# SMARC_CON.net
KiCad netlist of a schematic drawn in Altium Designer
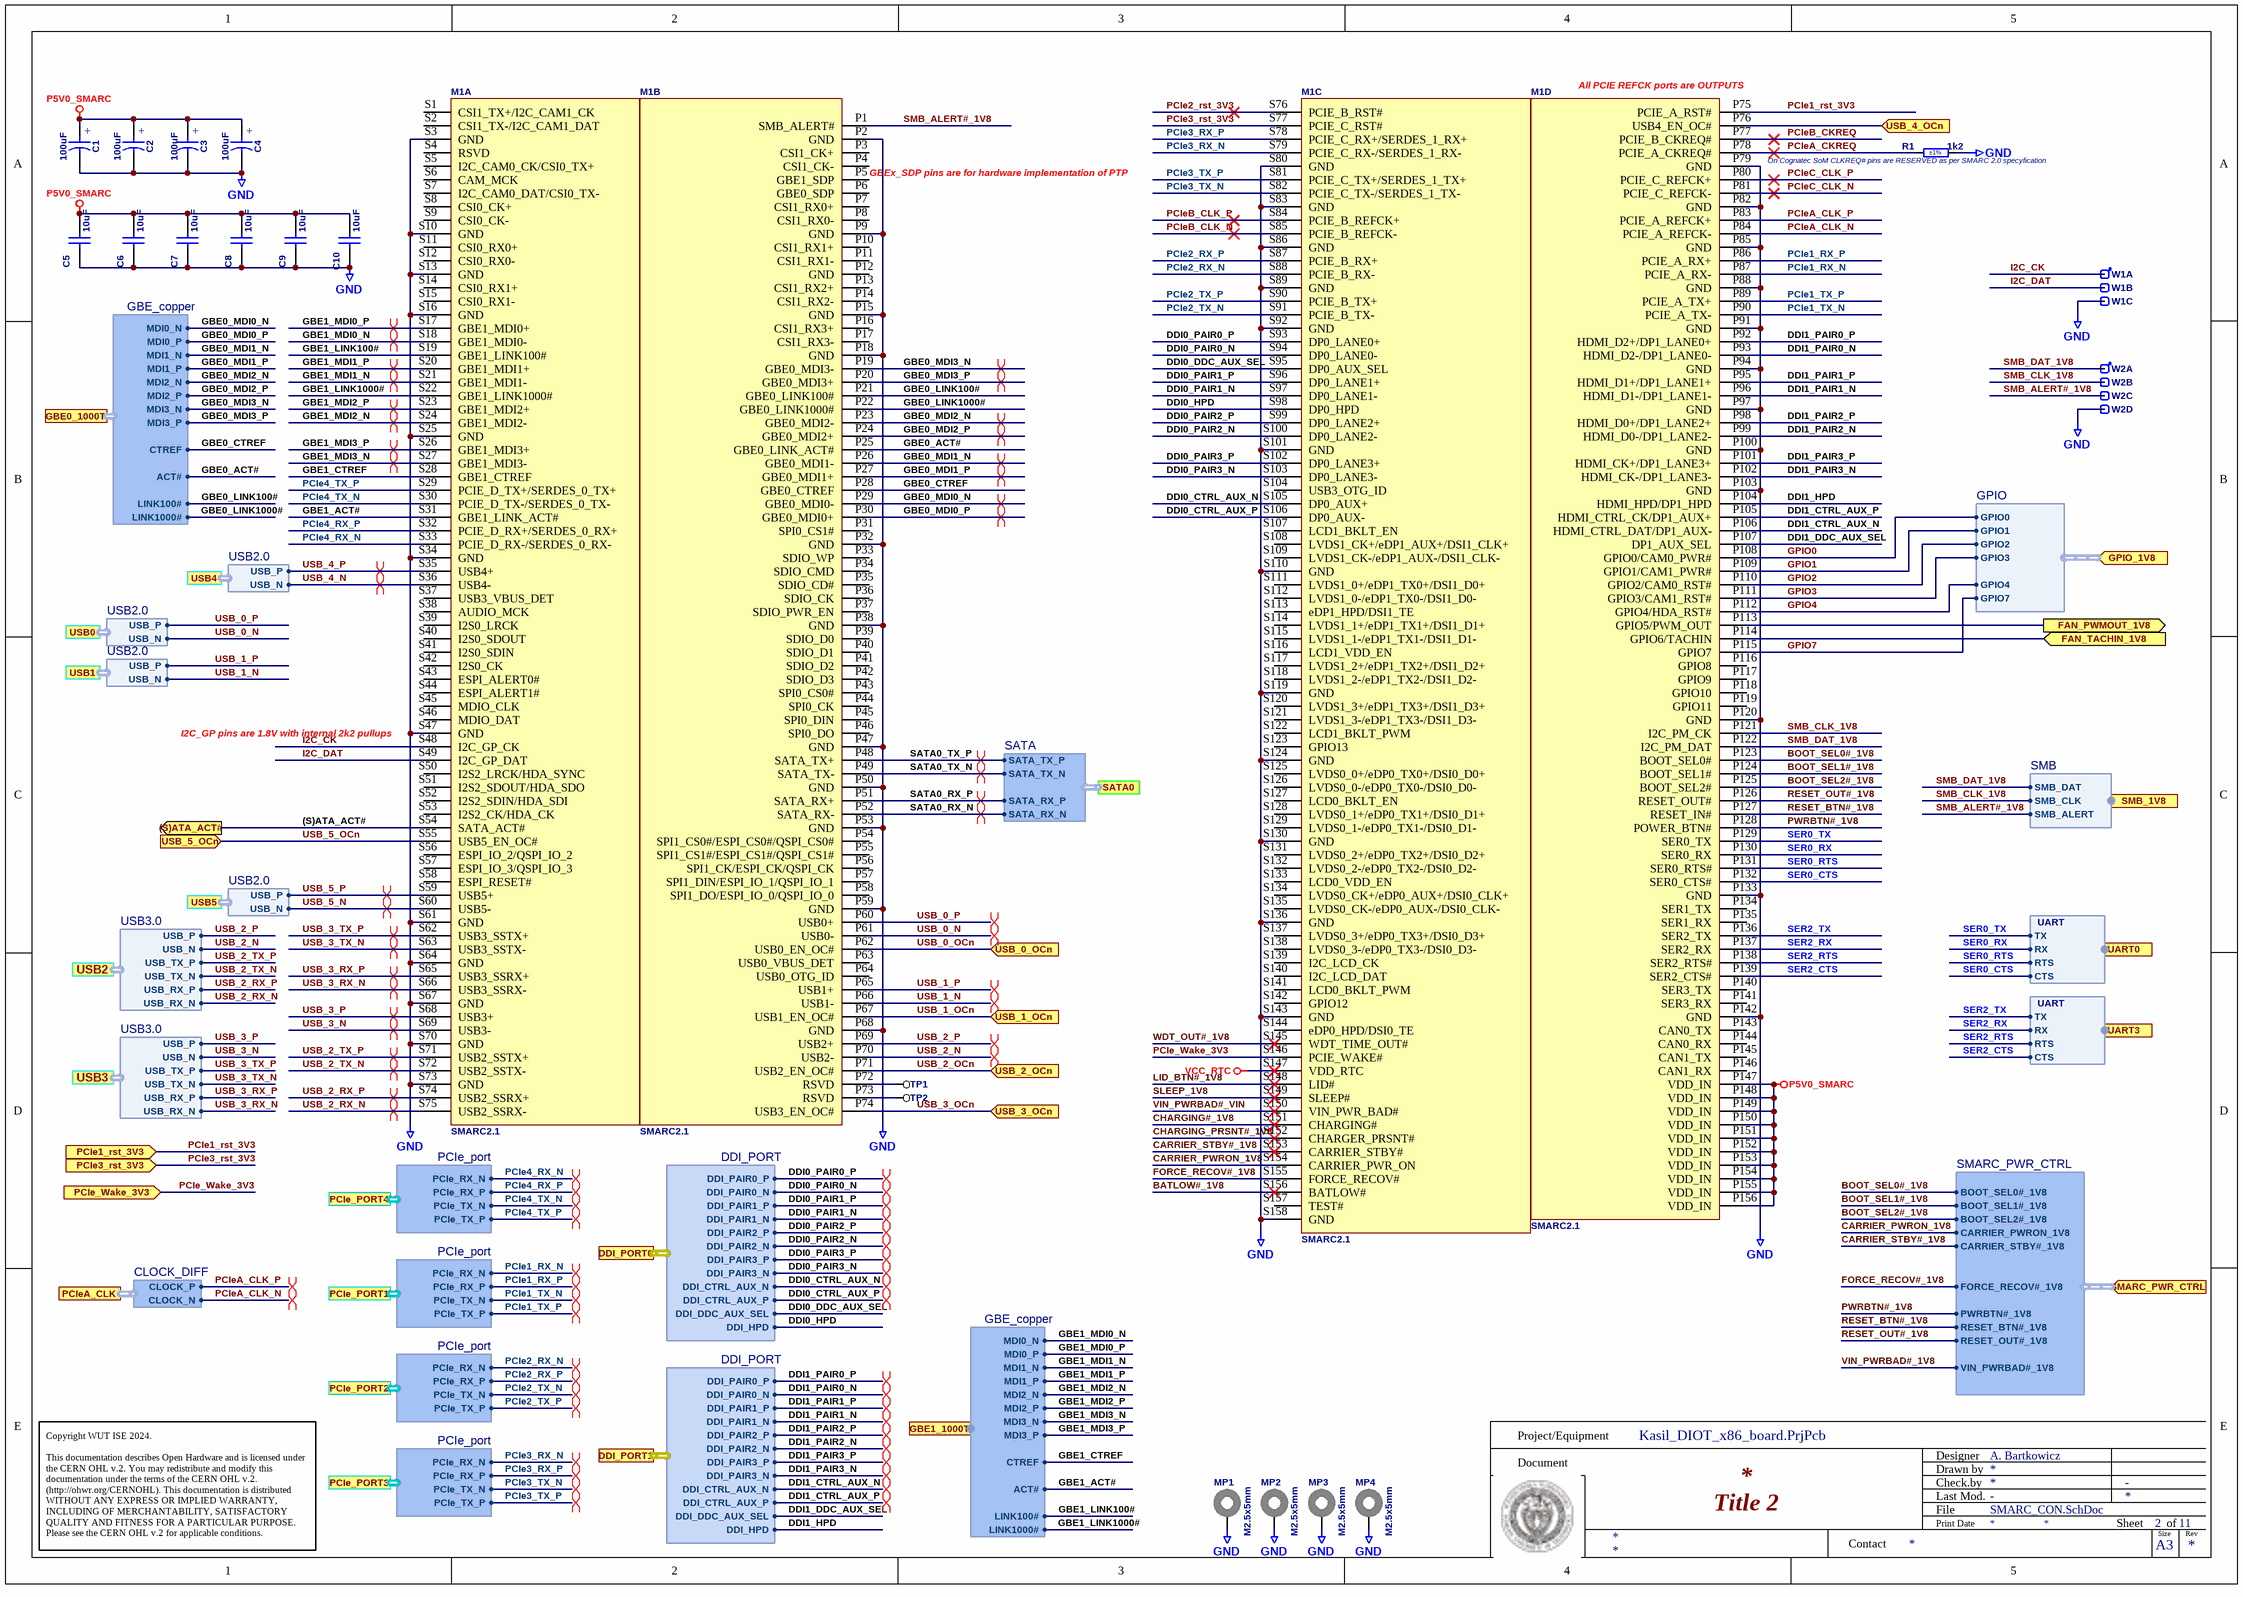
[diagram p0: SMARC_CON.SchDoc]

(export (version "E")
  (design (tool "Eeschema 10.0.6"))
  (components
    (comp (ref "C1")
      (value "100uF")
      (footprint "CAPMP7343X310N")
      (description "Polarised capacitor")
      (fields
        (field (name "PART NUMBER") "CTE7343-31_100UF_16V_10%_LESR0100")
        (field (name "VOLTAGE") "16V")
        (field (name "AUTHOR") "CERN DEM JLC")
      )
      (libsource (lib "Capacitors") (part "Capacitor - polarized"))
    )
    (comp (ref "C2")
      (value "100uF")
      (footprint "CAPMP7343X310N")
      (description "Polarised capacitor")
      (fields
        (field (name "PART NUMBER") "CTE7343-31_100UF_16V_10%_LESR0100")
        (field (name "VOLTAGE") "16V")
        (field (name "AUTHOR") "CERN DEM JLC")
      )
      (libsource (lib "Capacitors") (part "Capacitor - polarized"))
    )
    (comp (ref "C3")
      (value "100uF")
      (footprint "CAPMP7343X310N")
      (description "Polarised capacitor")
      (fields
        (field (name "PART NUMBER") "CTE7343-31_100UF_16V_10%_LESR0100")
        (field (name "VOLTAGE") "16V")
        (field (name "AUTHOR") "CERN DEM JLC")
      )
      (libsource (lib "Capacitors") (part "Capacitor - polarized"))
    )
    (comp (ref "C4")
      (value "100uF")
      (footprint "CAPMP7343X310N")
      (description "Polarised capacitor")
      (fields
        (field (name "PART NUMBER") "CTE7343-31_100UF_16V_10%_LESR0100")
        (field (name "VOLTAGE") "16V")
        (field (name "AUTHOR") "CERN DEM JLC")
      )
      (libsource (lib "Capacitors") (part "Capacitor - polarized"))
    )
    (comp (ref "C5")
      (value "10uF")
      (footprint "CAPC1608X80N")
      (description "Non-polarised capacitor")
      (fields
        (field (name "PART NUMBER") "CC0603_10UF_16V_20%_X5R")
        (field (name "VOLTAGE") "16V")
        (field (name "AUTHOR") "CERN DEM MR")
      )
      (libsource (lib "Capacitors") (part "Capacitor - non polarized"))
    )
    (comp (ref "C6")
      (value "10uF")
      (footprint "CAPC1608X80N")
      (description "Non-polarised capacitor")
      (fields
        (field (name "PART NUMBER") "CC0603_10UF_16V_20%_X5R")
        (field (name "VOLTAGE") "16V")
        (field (name "AUTHOR") "CERN DEM MR")
      )
      (libsource (lib "Capacitors") (part "Capacitor - non polarized"))
    )
    (comp (ref "C7")
      (value "10uF")
      (footprint "CAPC1608X80N")
      (description "Non-polarised capacitor")
      (fields
        (field (name "PART NUMBER") "CC0603_10UF_16V_20%_X5R")
        (field (name "VOLTAGE") "16V")
        (field (name "AUTHOR") "CERN DEM MR")
      )
      (libsource (lib "Capacitors") (part "Capacitor - non polarized"))
    )
    (comp (ref "C8")
      (value "10uF")
      (footprint "CAPC1608X80N")
      (description "Non-polarised capacitor")
      (fields
        (field (name "PART NUMBER") "CC0603_10UF_16V_20%_X5R")
        (field (name "VOLTAGE") "16V")
        (field (name "AUTHOR") "CERN DEM MR")
      )
      (libsource (lib "Capacitors") (part "Capacitor - non polarized"))
    )
    (comp (ref "C9")
      (value "10uF")
      (footprint "CAPC1608X80N")
      (description "Non-polarised capacitor")
      (fields
        (field (name "PART NUMBER") "CC0603_10UF_16V_20%_X5R")
        (field (name "VOLTAGE") "16V")
        (field (name "AUTHOR") "CERN DEM MR")
      )
      (libsource (lib "Capacitors") (part "Capacitor - non polarized"))
    )
    (comp (ref "C10")
      (value "10uF")
      (footprint "CAPC1608X80N")
      (description "Non-polarised capacitor")
      (fields
        (field (name "PART NUMBER") "CC0603_10UF_16V_20%_X5R")
        (field (name "VOLTAGE") "16V")
        (field (name "AUTHOR") "CERN DEM MR")
      )
      (libsource (lib "Capacitors") (part "Capacitor - non polarized"))
    )
    (comp (ref "M1") (value "SMARC2.1") (footprint "SMARC2.1") (libsource (lib "") (part "SMARC2.1_1")))
    (comp (ref "MP1")
      (value "M2.5x5mm")
      (footprint "9774025151")
      (description "WA-SMSI SMT Steel Spacer, internal Thread, OD 5.1mm, M2.5x5mm")
      (fields (field (name "MANUFACTURER 1 PART NUMBER") "9774050151R"))
      (libsource (lib "Altium_WA-SMSI (rev21a)") (part "9774050151R"))
    )
    (comp (ref "MP2")
      (value "M2.5x5mm")
      (footprint "9774025151")
      (description "WA-SMSI SMT Steel Spacer, internal Thread, OD 5.1mm, M2.5x5mm")
      (fields (field (name "MANUFACTURER 1 PART NUMBER") "9774050151R"))
      (libsource (lib "Altium_WA-SMSI (rev21a)") (part "9774050151R"))
    )
    (comp (ref "MP3")
      (value "M2.5x5mm")
      (footprint "9774025151")
      (description "WA-SMSI SMT Steel Spacer, internal Thread, OD 5.1mm, M2.5x5mm")
      (fields (field (name "MANUFACTURER 1 PART NUMBER") "9774050151R"))
      (libsource (lib "Altium_WA-SMSI (rev21a)") (part "9774050151R"))
    )
    (comp (ref "MP4")
      (value "M2.5x5mm")
      (footprint "9774025151")
      (description "WA-SMSI SMT Steel Spacer, internal Thread, OD 5.1mm, M2.5x5mm")
      (fields (field (name "MANUFACTURER 1 PART NUMBER") "9774050151R"))
      (libsource (lib "Altium_WA-SMSI (rev21a)") (part "9774050151R"))
    )
    (comp (ref "R1")
      (value "1k2")
      (footprint "RESC1005X40N")
      (description "Resistor - 1%")
      (fields
        (field (name "TOLERANCE") "±1%")
        (field (name "PART NUMBER") "R0402_1K2_1%_0.0625W_100PPM")
        (field (name "POWER") "0.0625W")
        (field (name "AUTHOR") "CERN DEM JLC")
      )
      (libsource (lib "Resistors") (part "Resistor - 1%"))
    )
    (comp (ref "TP1")
      (value "TP")
      (footprint "TP_large")
      (description "Testpoint")
      (libsource (lib "LIBRARY_SCH") (part "TP"))
    )
    (comp (ref "TP2")
      (value "TP")
      (footprint "TP_large")
      (description "Testpoint")
      (libsource (lib "LIBRARY_SCH") (part "TP"))
    )
    (comp (ref "W1")
      (value "Header 3")
      (footprint "SAMTEC_TSW-103-23-L-S")
      (description "3 Mini Wire-Wrap Contact Strip Header")
      (fields
        (field (name "PART NUMBER") "SAMTEC_TSW-103-23-L-S")
        (field (name "MANUFACTURER") "SAMTEC")
        (field (name "AUTHOR") "CERN DEM JLC")
      )
      (libsource (lib "Connectors") (part "Wire-Wrap Contact x3"))
    )
    (comp (ref "W2")
      (value "Header 4")
      (footprint "SAMTEC_TSW-104-23-L-S")
      (description "4 Mini Wire-Wrap Contact Strip Header")
      (fields
        (field (name "PART NUMBER") "SAMTEC_TSW-104-23-L-S")
        (field (name "MANUFACTURER") "SAMTEC")
        (field (name "AUTHOR") "CERN DEM JLC")
      )
      (libsource (lib "Connectors") (part "Wire-Wrap Contact x4"))
    )
  )
  (nets
    (net (code "12") (name "/(S)ATA_ACT#") (class "Default")
      (node (ref "M1") (pin "S54") (pinfunction "SATA_ACT#_S54") (pintype "passive"))
    )
    (net (code "13") (name "/BATLOW#_1V8") (class "Default")
      (node (ref "M1") (pin "S156") (pinfunction "BATLOW#_S156") (pintype "passive+no_connect"))
    )
    (net (code "14") (name "/BOOT_SEL0#_1V8") (class "Default")
      (node (ref "M1") (pin "P123") (pinfunction "BOOT_SEL0#_P123") (pintype "passive"))
    )
    (net (code "15") (name "/BOOT_SEL1#_1V8") (class "Default")
      (node (ref "M1") (pin "P124") (pinfunction "BOOT_SEL1#_P124") (pintype "passive"))
    )
    (net (code "16") (name "/BOOT_SEL2#_1V8") (class "Default")
      (node (ref "M1") (pin "P125") (pinfunction "BOOT_SEL2#_P125") (pintype "passive"))
    )
    (net (code "17") (name "/CARRIER_PWRON_1V8") (class "Default")
      (node (ref "M1") (pin "S154") (pinfunction "CARRIER_PWR_ON_S154") (pintype "passive"))
    )
    (net (code "18") (name "/CARRIER_STBY#_1V8") (class "Default")
      (node (ref "M1") (pin "S153") (pinfunction "CARRIER_STBY#_S153") (pintype "passive+no_connect"))
    )
    (net (code "19") (name "/CHARGING#_1V8") (class "Default")
      (node (ref "M1") (pin "S151") (pinfunction "CHARGING#_S151") (pintype "passive+no_connect"))
    )
    (net (code "20") (name "/CHARGING_PRSNT#_1V8") (class "Default")
      (node (ref "M1") (pin "S152") (pinfunction "CHARGER_PRSNT#_S152") (pintype "passive+no_connect"))
    )
    (net (code "21") (name "/DDI0_CTRL_AUX_N") (class "Default")
      (node (ref "M1") (pin "S105") (pinfunction "DP0_AUX+_S105") (pintype "passive"))
    )
    (net (code "22") (name "/DDI0_CTRL_AUX_P") (class "Default")
      (node (ref "M1") (pin "S106") (pinfunction "DP0_AUX-_S106") (pintype "passive"))
    )
    (net (code "23") (name "/DDI0_DDC_AUX_SEL") (class "Default")
      (node (ref "M1") (pin "S95") (pinfunction "DP0_AUX_SEL_S95") (pintype "passive"))
    )
    (net (code "24") (name "/DDI0_HPD") (class "Default")
      (node (ref "M1") (pin "S98") (pinfunction "DP0_HPD_S98") (pintype "passive"))
    )
    (net (code "25") (name "/DDI0_PAIR0_N") (class "Default")
      (node (ref "M1") (pin "S94") (pinfunction "DP0_LANE0-_S94") (pintype "passive"))
    )
    (net (code "26") (name "/DDI0_PAIR0_P") (class "Default")
      (node (ref "M1") (pin "S93") (pinfunction "DP0_LANE0+_S93") (pintype "passive"))
    )
    (net (code "27") (name "/DDI0_PAIR1_N") (class "Default")
      (node (ref "M1") (pin "S97") (pinfunction "DP0_LANE1-_S97") (pintype "passive"))
    )
    (net (code "28") (name "/DDI0_PAIR1_P") (class "Default")
      (node (ref "M1") (pin "S96") (pinfunction "DP0_LANE1+_S96") (pintype "passive"))
    )
    (net (code "29") (name "/DDI0_PAIR2_N") (class "Default")
      (node (ref "M1") (pin "S100") (pinfunction "DP0_LANE2-_S100") (pintype "passive"))
    )
    (net (code "30") (name "/DDI0_PAIR2_P") (class "Default")
      (node (ref "M1") (pin "S99") (pinfunction "DP0_LANE2+_S99") (pintype "passive"))
    )
    (net (code "31") (name "/DDI0_PAIR3_N") (class "Default")
      (node (ref "M1") (pin "S103") (pinfunction "DP0_LANE3-_S103") (pintype "passive"))
    )
    (net (code "32") (name "/DDI0_PAIR3_P") (class "Default")
      (node (ref "M1") (pin "S102") (pinfunction "DP0_LANE3+_S102") (pintype "passive"))
    )
    (net (code "33") (name "/DDI1_CTRL_AUX_N") (class "Default")
      (node (ref "M1") (pin "P106") (pinfunction "HDMI_CTRL_DAT/DP1_AUX-_P106") (pintype "passive"))
    )
    (net (code "34") (name "/DDI1_CTRL_AUX_P") (class "Default")
      (node (ref "M1") (pin "P105") (pinfunction "HDMI_CTRL_CK/DP1_AUX+_P105") (pintype "passive"))
    )
    (net (code "35") (name "/DDI1_DDC_AUX_SEL") (class "Default")
      (node (ref "M1") (pin "P107") (pinfunction "DP1_AUX_SEL_P107") (pintype "passive"))
    )
    (net (code "36") (name "/DDI1_HPD") (class "Default")
      (node (ref "M1") (pin "P104") (pinfunction "HDMI_HPD/DP1_HPD_P104") (pintype "passive"))
    )
    (net (code "37") (name "/DDI1_PAIR0_N") (class "Default")
      (node (ref "M1") (pin "P93") (pinfunction "HDMI_D2-/DP1_LANE0-_P93") (pintype "passive"))
    )
    (net (code "38") (name "/DDI1_PAIR0_P") (class "Default")
      (node (ref "M1") (pin "P92") (pinfunction "HDMI_D2+/DP1_LANE0+_P92") (pintype "passive"))
    )
    (net (code "39") (name "/DDI1_PAIR1_N") (class "Default")
      (node (ref "M1") (pin "P96") (pinfunction "HDMI_D1-/DP1_LANE1-_P96") (pintype "passive"))
    )
    (net (code "40") (name "/DDI1_PAIR1_P") (class "Default")
      (node (ref "M1") (pin "P95") (pinfunction "HDMI_D1+/DP1_LANE1+_P95") (pintype "passive"))
    )
    (net (code "41") (name "/DDI1_PAIR2_N") (class "Default")
      (node (ref "M1") (pin "P99") (pinfunction "HDMI_D0-/DP1_LANE2-_P99") (pintype "passive"))
    )
    (net (code "42") (name "/DDI1_PAIR2_P") (class "Default")
      (node (ref "M1") (pin "P98") (pinfunction "HDMI_D0+/DP1_LANE2+_P98") (pintype "passive"))
    )
    (net (code "43") (name "/DDI1_PAIR3_N") (class "Default")
      (node (ref "M1") (pin "P102") (pinfunction "HDMI_CK-/DP1_LANE3-_P102") (pintype "passive"))
    )
    (net (code "44") (name "/DDI1_PAIR3_P") (class "Default")
      (node (ref "M1") (pin "P101") (pinfunction "HDMI_CK+/DP1_LANE3+_P101") (pintype "passive"))
    )
    (net (code "45") (name "/FAN_PWMOUT_1V8") (class "Default")
      (node (ref "M1") (pin "P113") (pinfunction "GPIO5/PWM_OUT_P113") (pintype "passive"))
    )
    (net (code "46") (name "/FAN_TACHIN_1V8") (class "Default")
      (node (ref "M1") (pin "P114") (pinfunction "GPIO6/TACHIN_P114") (pintype "passive"))
    )
    (net (code "47") (name "/FORCE_RECOV#_1V8") (class "Default")
      (node (ref "M1") (pin "S155") (pinfunction "FORCE_RECOV#_S155") (pintype "passive"))
    )
    (net (code "48") (name "/GBE0_ACT#") (class "Default")
      (node (ref "M1") (pin "P25") (pinfunction "GBE0_LINK_ACT#_P25") (pintype "passive"))
    )
    (net (code "49") (name "/GBE0_CTREF") (class "Default")
      (node (ref "M1") (pin "P28") (pinfunction "GBE0_CTREF_P28") (pintype "passive"))
    )
    (net (code "50") (name "/GBE0_LINK100#") (class "Default")
      (node (ref "M1") (pin "P21") (pinfunction "GBE0_LINK100#_P21") (pintype "passive"))
    )
    (net (code "51") (name "/GBE0_LINK1000#") (class "Default")
      (node (ref "M1") (pin "P22") (pinfunction "GBE0_LINK1000#_P22") (pintype "passive"))
    )
    (net (code "52") (name "/GBE0_MDI0_N") (class "Default")
      (node (ref "M1") (pin "P29") (pinfunction "GBE0_MDI0-_P29") (pintype "passive"))
    )
    (net (code "53") (name "/GBE0_MDI0_P") (class "Default")
      (node (ref "M1") (pin "P30") (pinfunction "GBE0_MDI0+_P30") (pintype "passive"))
    )
    (net (code "54") (name "/GBE0_MDI1_N") (class "Default")
      (node (ref "M1") (pin "P26") (pinfunction "GBE0_MDI1-_P26") (pintype "passive"))
    )
    (net (code "55") (name "/GBE0_MDI1_P") (class "Default")
      (node (ref "M1") (pin "P27") (pinfunction "GBE0_MDI1+_P27") (pintype "passive"))
    )
    (net (code "56") (name "/GBE0_MDI2_N") (class "Default")
      (node (ref "M1") (pin "P23") (pinfunction "GBE0_MDI2-_P23") (pintype "passive"))
    )
    (net (code "57") (name "/GBE0_MDI2_P") (class "Default")
      (node (ref "M1") (pin "P24") (pinfunction "GBE0_MDI2+_P24") (pintype "passive"))
    )
    (net (code "58") (name "/GBE0_MDI3_N") (class "Default")
      (node (ref "M1") (pin "P19") (pinfunction "GBE0_MDI3-_P19") (pintype "passive"))
    )
    (net (code "59") (name "/GBE0_MDI3_P") (class "Default")
      (node (ref "M1") (pin "P20") (pinfunction "GBE0_MDI3+_P20") (pintype "passive"))
    )
    (net (code "60") (name "/GBE1_ACT#") (class "Default")
      (node (ref "M1") (pin "S31") (pinfunction "GBE1_LINK_ACT#_S31") (pintype "passive"))
    )
    (net (code "61") (name "/GBE1_CTREF") (class "Default")
      (node (ref "M1") (pin "S28") (pinfunction "GBE1_CTREF_S28") (pintype "passive"))
    )
    (net (code "62") (name "/GBE1_LINK100#") (class "Default")
      (node (ref "M1") (pin "S19") (pinfunction "GBE1_LINK100#_S19") (pintype "passive"))
    )
    (net (code "63") (name "/GBE1_LINK1000#") (class "Default")
      (node (ref "M1") (pin "S22") (pinfunction "GBE1_LINK1000#_S22") (pintype "passive"))
    )
    (net (code "64") (name "/GBE1_MDI0_N") (class "Default")
      (node (ref "M1") (pin "S18") (pinfunction "GBE1_MDI0-_S18") (pintype "passive"))
    )
    (net (code "65") (name "/GBE1_MDI0_P") (class "Default")
      (node (ref "M1") (pin "S17") (pinfunction "GBE1_MDI0+_S17") (pintype "passive"))
    )
    (net (code "66") (name "/GBE1_MDI1_N") (class "Default")
      (node (ref "M1") (pin "S21") (pinfunction "GBE1_MDI1-_S21") (pintype "passive"))
    )
    (net (code "67") (name "/GBE1_MDI1_P") (class "Default")
      (node (ref "M1") (pin "S20") (pinfunction "GBE1_MDI1+_S20") (pintype "passive"))
    )
    (net (code "68") (name "/GBE1_MDI2_N") (class "Default")
      (node (ref "M1") (pin "S24") (pinfunction "GBE1_MDI2-_S24") (pintype "passive"))
    )
    (net (code "69") (name "/GBE1_MDI2_P") (class "Default")
      (node (ref "M1") (pin "S23") (pinfunction "GBE1_MDI2+_S23") (pintype "passive"))
    )
    (net (code "70") (name "/GBE1_MDI3_N") (class "Default")
      (node (ref "M1") (pin "S27") (pinfunction "GBE1_MDI3-_S27") (pintype "passive"))
    )
    (net (code "71") (name "/GBE1_MDI3_P") (class "Default")
      (node (ref "M1") (pin "S26") (pinfunction "GBE1_MDI3+_S26") (pintype "passive"))
    )
    (net (code "72") (name "/GPIO0") (class "Default")
      (node (ref "M1") (pin "P108") (pinfunction "GPIO0/CAM0_PWR#_P108") (pintype "passive"))
    )
    (net (code "73") (name "/GPIO1") (class "Default")
      (node (ref "M1") (pin "P109") (pinfunction "GPIO1/CAM1_PWR#_P109") (pintype "passive"))
    )
    (net (code "74") (name "/GPIO2") (class "Default")
      (node (ref "M1") (pin "P110") (pinfunction "GPIO2/CAM0_RST#_P110") (pintype "passive"))
    )
    (net (code "75") (name "/GPIO3") (class "Default")
      (node (ref "M1") (pin "P111") (pinfunction "GPIO3/CAM1_RST#_P111") (pintype "passive"))
    )
    (net (code "76") (name "/GPIO4") (class "Default")
      (node (ref "M1") (pin "P112") (pinfunction "GPIO4/HDA_RST#_P112") (pintype "passive"))
    )
    (net (code "77") (name "/GPIO7") (class "Default")
      (node (ref "M1") (pin "P115") (pinfunction "GPIO7_P115") (pintype "passive"))
    )
    (net (code "78") (name "/I2C_CK") (class "Default")
      (node (ref "M1") (pin "S48") (pinfunction "I2C_GP_CK_S48") (pintype "passive"))
      (node (ref "W1") (pin "1") (pinfunction "1_1") (pintype "bidirectional"))
    )
    (net (code "79") (name "/I2C_DAT") (class "Default")
      (node (ref "M1") (pin "S49") (pinfunction "I2C_GP_DAT_S49") (pintype "passive"))
      (node (ref "W1") (pin "2") (pinfunction "2_2") (pintype "bidirectional"))
    )
    (net (code "80") (name "/LID_BTN#_1V8") (class "Default")
      (node (ref "M1") (pin "S148") (pinfunction "LID#_S148") (pintype "passive+no_connect"))
    )
    (net (code "81") (name "/PCIe1_RX_N") (class "Default")
      (node (ref "M1") (pin "P87") (pinfunction "PCIE_A_RX-_P87") (pintype "passive"))
    )
    (net (code "82") (name "/PCIe1_RX_P") (class "Default")
      (node (ref "M1") (pin "P86") (pinfunction "PCIE_A_RX+_P86") (pintype "passive"))
    )
    (net (code "83") (name "/PCIe1_TX_N") (class "Default")
      (node (ref "M1") (pin "P90") (pinfunction "PCIE_A_TX-_P90") (pintype "passive"))
    )
    (net (code "84") (name "/PCIe1_TX_P") (class "Default")
      (node (ref "M1") (pin "P89") (pinfunction "PCIE_A_TX+_P89") (pintype "passive"))
    )
    (net (code "85") (name "/PCIe1_rst_3V3") (class "Default")
      (node (ref "M1") (pin "P75") (pinfunction "PCIE_A_RST#_P75") (pintype "passive"))
    )
    (net (code "86") (name "/PCIe2_RX_N") (class "Default")
      (node (ref "M1") (pin "S88") (pinfunction "PCIE_B_RX-_S88") (pintype "passive"))
    )
    (net (code "87") (name "/PCIe2_RX_P") (class "Default")
      (node (ref "M1") (pin "S87") (pinfunction "PCIE_B_RX+_S87") (pintype "passive"))
    )
    (net (code "88") (name "/PCIe2_TX_N") (class "Default")
      (node (ref "M1") (pin "S91") (pinfunction "PCIE_B_TX-_S91") (pintype "passive"))
    )
    (net (code "89") (name "/PCIe2_TX_P") (class "Default")
      (node (ref "M1") (pin "S90") (pinfunction "PCIE_B_TX+_S90") (pintype "passive"))
    )
    (net (code "90") (name "/PCIe2_rst_3V3") (class "Default")
      (node (ref "M1") (pin "S76") (pinfunction "PCIE_B_RST#_S76") (pintype "passive"))
    )
    (net (code "91") (name "/PCIe3_RX_N") (class "Default")
      (node (ref "M1") (pin "S79") (pinfunction "PCIE_C_RX-/SERDES_1_RX-_S79") (pintype "passive"))
    )
    (net (code "92") (name "/PCIe3_RX_P") (class "Default")
      (node (ref "M1") (pin "S78") (pinfunction "PCIE_C_RX+/SERDES_1_RX+_S78") (pintype "passive"))
    )
    (net (code "93") (name "/PCIe3_TX_N") (class "Default")
      (node (ref "M1") (pin "S82") (pinfunction "PCIE_C_TX-/SERDES_1_TX-_S82") (pintype "passive"))
    )
    (net (code "94") (name "/PCIe3_TX_P") (class "Default")
      (node (ref "M1") (pin "S81") (pinfunction "PCIE_C_TX+/SERDES_1_TX+_S81") (pintype "passive"))
    )
    (net (code "95") (name "/PCIe3_rst_3V3") (class "Default")
      (node (ref "M1") (pin "S77") (pinfunction "PCIE_C_RST#_S77") (pintype "passive"))
    )
    (net (code "96") (name "/PCIe4_RX_N") (class "Default")
      (node (ref "M1") (pin "S33") (pinfunction "PCIE_D_RX-/SERDES_0_RX-_S33") (pintype "passive"))
    )
    (net (code "97") (name "/PCIe4_RX_P") (class "Default")
      (node (ref "M1") (pin "S32") (pinfunction "PCIE_D_RX+/SERDES_0_RX+_S32") (pintype "passive"))
    )
    (net (code "98") (name "/PCIe4_TX_N") (class "Default")
      (node (ref "M1") (pin "S30") (pinfunction "PCIE_D_TX-/SERDES_0_TX-_S30") (pintype "passive"))
    )
    (net (code "99") (name "/PCIe4_TX_P") (class "Default")
      (node (ref "M1") (pin "S29") (pinfunction "PCIE_D_TX+/SERDES_0_TX+_S29") (pintype "passive"))
    )
    (net (code "100") (name "/PCIeA_CKREQ") (class "Default")
      (node (ref "M1") (pin "P78") (pinfunction "PCIE_A_CKREQ#_P78") (pintype "passive"))
      (node (ref "R1") (pin "1") (pinfunction "1_1") (pintype "passive"))
    )
    (net (code "101") (name "/PCIeA_CLK_N") (class "Default")
      (node (ref "M1") (pin "P84") (pinfunction "PCIE_A_REFCK-_P84") (pintype "passive"))
    )
    (net (code "102") (name "/PCIeA_CLK_P") (class "Default")
      (node (ref "M1") (pin "P83") (pinfunction "PCIE_A_REFCK+_P83") (pintype "passive"))
    )
    (net (code "103") (name "/PCIeB_CKREQ") (class "Default")
      (node (ref "M1") (pin "P77") (pinfunction "PCIE_B_CKREQ#_P77") (pintype "passive"))
    )
    (net (code "104") (name "/PCIeB_CLK_N") (class "Default")
      (node (ref "M1") (pin "S85") (pinfunction "PCIE_B_REFCK-_S85") (pintype "passive"))
    )
    (net (code "105") (name "/PCIeB_CLK_P") (class "Default")
      (node (ref "M1") (pin "S84") (pinfunction "PCIE_B_REFCK+_S84") (pintype "passive"))
    )
    (net (code "106") (name "/PCIeC_CLK_N") (class "Default")
      (node (ref "M1") (pin "P81") (pinfunction "PCIE_C_REFCK-_P81") (pintype "passive"))
    )
    (net (code "107") (name "/PCIeC_CLK_P") (class "Default")
      (node (ref "M1") (pin "P80") (pinfunction "PCIE_C_REFCK+_P80") (pintype "passive"))
    )
    (net (code "108") (name "/PCIe_Wake_3V3") (class "Default")
      (node (ref "M1") (pin "S146") (pinfunction "PCIE_WAKE#_S146") (pintype "passive"))
    )
    (net (code "109") (name "/PWRBTN#_1V8") (class "Default")
      (node (ref "M1") (pin "P128") (pinfunction "POWER_BTN#_P128") (pintype "passive"))
    )
    (net (code "110") (name "/RESET_BTN#_1V8") (class "Default")
      (node (ref "M1") (pin "P127") (pinfunction "RESET_IN#_P127") (pintype "passive"))
    )
    (net (code "111") (name "/RESET_OUT#_1V8") (class "Default")
      (node (ref "M1") (pin "P126") (pinfunction "RESET_OUT#_P126") (pintype "passive"))
    )
    (net (code "112") (name "/SATA0_RX_N") (class "Default")
      (node (ref "M1") (pin "P52") (pinfunction "SATA_RX-_P52") (pintype "passive"))
    )
    (net (code "113") (name "/SATA0_RX_P") (class "Default")
      (node (ref "M1") (pin "P51") (pinfunction "SATA_RX+_P51") (pintype "passive"))
    )
    (net (code "114") (name "/SATA0_TX_N") (class "Default")
      (node (ref "M1") (pin "P49") (pinfunction "SATA_TX-_P49") (pintype "passive"))
    )
    (net (code "115") (name "/SATA0_TX_P") (class "Default")
      (node (ref "M1") (pin "P48") (pinfunction "SATA_TX+_P48") (pintype "passive"))
    )
    (net (code "116") (name "/SER0_CTS") (class "Default")
      (node (ref "M1") (pin "P132") (pinfunction "SER0_CTS#_P132") (pintype "passive"))
    )
    (net (code "117") (name "/SER0_RTS") (class "Default")
      (node (ref "M1") (pin "P131") (pinfunction "SER0_RTS#_P131") (pintype "passive"))
    )
    (net (code "118") (name "/SER0_RX") (class "Default")
      (node (ref "M1") (pin "P130") (pinfunction "SER0_RX_P130") (pintype "passive"))
    )
    (net (code "119") (name "/SER0_TX") (class "Default")
      (node (ref "M1") (pin "P129") (pinfunction "SER0_TX_P129") (pintype "passive"))
    )
    (net (code "120") (name "/SER2_CTS") (class "Default")
      (node (ref "M1") (pin "P139") (pinfunction "SER2_CTS#_P139") (pintype "passive"))
    )
    (net (code "121") (name "/SER2_RTS") (class "Default")
      (node (ref "M1") (pin "P138") (pinfunction "SER2_RTS#_P138") (pintype "passive"))
    )
    (net (code "122") (name "/SER2_RX") (class "Default")
      (node (ref "M1") (pin "P137") (pinfunction "SER2_RX_P137") (pintype "passive"))
    )
    (net (code "123") (name "/SER2_TX") (class "Default")
      (node (ref "M1") (pin "P136") (pinfunction "SER2_TX_P136") (pintype "passive"))
    )
    (net (code "124") (name "/SLEEP_1V8") (class "Default")
      (node (ref "M1") (pin "S149") (pinfunction "SLEEP#_S149") (pintype "passive+no_connect"))
    )
    (net (code "125") (name "/SMB_ALERT#_1V8") (class "Default")
      (node (ref "M1") (pin "P1") (pinfunction "SMB_ALERT#_P1") (pintype "passive"))
      (node (ref "W2") (pin "3") (pinfunction "3_3") (pintype "bidirectional"))
    )
    (net (code "126") (name "/SMB_CLK_1V8") (class "Default")
      (node (ref "M1") (pin "P121") (pinfunction "I2C_PM_CK_P121") (pintype "passive"))
      (node (ref "W2") (pin "2") (pinfunction "2_2") (pintype "bidirectional"))
    )
    (net (code "127") (name "/SMB_DAT_1V8") (class "Default")
      (node (ref "M1") (pin "P122") (pinfunction "I2C_PM_DAT_P122") (pintype "passive"))
      (node (ref "W2") (pin "1") (pinfunction "1_1") (pintype "bidirectional"))
    )
    (net (code "128") (name "/USB_0_N") (class "Default")
      (node (ref "M1") (pin "P61") (pinfunction "USB0-_P61") (pintype "passive"))
    )
    (net (code "129") (name "/USB_0_OCn") (class "Default")
      (node (ref "M1") (pin "P62") (pinfunction "USB0_EN_OC#_P62") (pintype "passive"))
    )
    (net (code "130") (name "/USB_0_P") (class "Default")
      (node (ref "M1") (pin "P60") (pinfunction "USB0+_P60") (pintype "passive"))
    )
    (net (code "131") (name "/USB_1_N") (class "Default")
      (node (ref "M1") (pin "P66") (pinfunction "USB1-_P66") (pintype "passive"))
    )
    (net (code "132") (name "/USB_1_OCn") (class "Default")
      (node (ref "M1") (pin "P67") (pinfunction "USB1_EN_OC#_P67") (pintype "passive"))
    )
    (net (code "133") (name "/USB_1_P") (class "Default")
      (node (ref "M1") (pin "P65") (pinfunction "USB1+_P65") (pintype "passive"))
    )
    (net (code "134") (name "/USB_2_N") (class "Default")
      (node (ref "M1") (pin "P70") (pinfunction "USB2-_P70") (pintype "passive"))
    )
    (net (code "135") (name "/USB_2_OCn") (class "Default")
      (node (ref "M1") (pin "P71") (pinfunction "USB2_EN_OC#_P71") (pintype "passive"))
    )
    (net (code "136") (name "/USB_2_P") (class "Default")
      (node (ref "M1") (pin "P69") (pinfunction "USB2+_P69") (pintype "passive"))
    )
    (net (code "137") (name "/USB_2_RX_N") (class "Default")
      (node (ref "M1") (pin "S75") (pinfunction "USB2_SSRX-_S75") (pintype "passive"))
    )
    (net (code "138") (name "/USB_2_RX_P") (class "Default")
      (node (ref "M1") (pin "S74") (pinfunction "USB2_SSRX+_S74") (pintype "passive"))
    )
    (net (code "139") (name "/USB_2_TX_N") (class "Default")
      (node (ref "M1") (pin "S72") (pinfunction "USB2_SSTX-_S72") (pintype "passive"))
    )
    (net (code "140") (name "/USB_2_TX_P") (class "Default")
      (node (ref "M1") (pin "S71") (pinfunction "USB2_SSTX+_S71") (pintype "passive"))
    )
    (net (code "141") (name "/USB_3_N") (class "Default")
      (node (ref "M1") (pin "S69") (pinfunction "USB3-_S69") (pintype "passive"))
    )
    (net (code "142") (name "/USB_3_OCn") (class "Default")
      (node (ref "M1") (pin "P74") (pinfunction "USB3_EN_OC#_P74") (pintype "passive"))
    )
    (net (code "143") (name "/USB_3_P") (class "Default")
      (node (ref "M1") (pin "S68") (pinfunction "USB3+_S68") (pintype "passive"))
    )
    (net (code "144") (name "/USB_3_RX_N") (class "Default")
      (node (ref "M1") (pin "S66") (pinfunction "USB3_SSRX-_S66") (pintype "passive"))
    )
    (net (code "145") (name "/USB_3_RX_P") (class "Default")
      (node (ref "M1") (pin "S65") (pinfunction "USB3_SSRX+_S65") (pintype "passive"))
    )
    (net (code "146") (name "/USB_3_TX_N") (class "Default")
      (node (ref "M1") (pin "S63") (pinfunction "USB3_SSTX-_S63") (pintype "passive"))
    )
    (net (code "147") (name "/USB_3_TX_P") (class "Default")
      (node (ref "M1") (pin "S62") (pinfunction "USB3_SSTX+_S62") (pintype "passive"))
    )
    (net (code "148") (name "/USB_4_N") (class "Default")
      (node (ref "M1") (pin "S36") (pinfunction "USB4-_S36") (pintype "passive"))
    )
    (net (code "149") (name "/USB_4_OCn") (class "Default")
      (node (ref "M1") (pin "P76") (pinfunction "USB4_EN_OC#_P76") (pintype "passive"))
    )
    (net (code "150") (name "/USB_4_P") (class "Default")
      (node (ref "M1") (pin "S35") (pinfunction "USB4+_S35") (pintype "passive"))
    )
    (net (code "151") (name "/USB_5_N") (class "Default")
      (node (ref "M1") (pin "S60") (pinfunction "USB5-_S60") (pintype "passive"))
    )
    (net (code "152") (name "/USB_5_OCn") (class "Default")
      (node (ref "M1") (pin "S55") (pinfunction "USB5_EN_OC#_S55") (pintype "passive"))
    )
    (net (code "153") (name "/USB_5_P") (class "Default")
      (node (ref "M1") (pin "S59") (pinfunction "USB5+_S59") (pintype "passive"))
    )
    (net (code "155") (name "/VIN_PWRBAD#_VIN") (class "Default")
      (node (ref "M1") (pin "S150") (pinfunction "VIN_PWR_BAD#_S150") (pintype "passive+no_connect"))
    )
    (net (code "156") (name "/WDT_OUT#_1V8") (class "Default")
      (node (ref "M1") (pin "S145") (pinfunction "WDT_TIME_OUT#_S145") (pintype "passive+no_connect"))
    )
    (net (code "168") (name "GND") (class "Default")
      (node (ref "C1") (pin "2") (pinfunction "2_2") (pintype "passive"))
      (node (ref "C10") (pin "1") (pinfunction "1_1") (pintype "passive"))
      (node (ref "C2") (pin "2") (pinfunction "2_2") (pintype "passive"))
      (node (ref "C3") (pin "2") (pinfunction "2_2") (pintype "passive"))
      (node (ref "C4") (pin "2") (pinfunction "2_2") (pintype "passive"))
      (node (ref "C5") (pin "1") (pinfunction "1_1") (pintype "passive"))
      (node (ref "C6") (pin "1") (pinfunction "1_1") (pintype "passive"))
      (node (ref "C7") (pin "1") (pinfunction "1_1") (pintype "passive"))
      (node (ref "C8") (pin "1") (pinfunction "1_1") (pintype "passive"))
      (node (ref "C9") (pin "1") (pinfunction "1_1") (pintype "passive"))
      (node (ref "M1") (pin "P100") (pinfunction "GND_P100") (pintype "passive"))
      (node (ref "M1") (pin "P103") (pinfunction "GND_P103") (pintype "passive"))
      (node (ref "M1") (pin "P120") (pinfunction "GND_P120") (pintype "passive"))
      (node (ref "M1") (pin "P133") (pinfunction "GND_P133") (pintype "passive"))
      (node (ref "M1") (pin "P142") (pinfunction "GND_P142") (pintype "passive"))
      (node (ref "M1") (pin "P15") (pinfunction "GND_P15") (pintype "passive"))
      (node (ref "M1") (pin "P18") (pinfunction "GND_P18") (pintype "passive"))
      (node (ref "M1") (pin "P2") (pinfunction "GND_P2") (pintype "passive"))
      (node (ref "M1") (pin "P32") (pinfunction "GND_P32") (pintype "passive"))
      (node (ref "M1") (pin "P38") (pinfunction "GND_P38") (pintype "passive"))
      (node (ref "M1") (pin "P47") (pinfunction "GND_P47") (pintype "passive"))
      (node (ref "M1") (pin "P50") (pinfunction "GND_P50") (pintype "passive"))
      (node (ref "M1") (pin "P53") (pinfunction "GND_P53") (pintype "passive"))
      (node (ref "M1") (pin "P59") (pinfunction "GND_P59") (pintype "passive"))
      (node (ref "M1") (pin "P68") (pinfunction "GND_P68") (pintype "passive"))
      (node (ref "M1") (pin "P79") (pinfunction "GND_P79") (pintype "passive"))
      (node (ref "M1") (pin "P82") (pinfunction "GND_P82") (pintype "passive"))
      (node (ref "M1") (pin "P85") (pinfunction "GND_P85") (pintype "passive"))
      (node (ref "M1") (pin "P88") (pinfunction "GND_P88") (pintype "passive"))
      (node (ref "M1") (pin "P9") (pinfunction "GND_P9") (pintype "passive"))
      (node (ref "M1") (pin "P91") (pinfunction "GND_P91") (pintype "passive"))
      (node (ref "M1") (pin "P94") (pinfunction "GND_P94") (pintype "passive"))
      (node (ref "M1") (pin "P97") (pinfunction "GND_P97") (pintype "passive"))
      (node (ref "M1") (pin "S10") (pinfunction "GND_S10") (pintype "passive"))
      (node (ref "M1") (pin "S101") (pinfunction "GND_S101") (pintype "passive"))
      (node (ref "M1") (pin "S110") (pinfunction "GND_S110") (pintype "passive"))
      (node (ref "M1") (pin "S119") (pinfunction "GND_S119") (pintype "passive"))
      (node (ref "M1") (pin "S124") (pinfunction "GND_S124") (pintype "passive"))
      (node (ref "M1") (pin "S13") (pinfunction "GND_S13") (pintype "passive"))
      (node (ref "M1") (pin "S130") (pinfunction "GND_S130") (pintype "passive"))
      (node (ref "M1") (pin "S136") (pinfunction "GND_S136") (pintype "passive"))
      (node (ref "M1") (pin "S143") (pinfunction "GND_S143") (pintype "passive"))
      (node (ref "M1") (pin "S158") (pinfunction "GND_S158") (pintype "passive"))
      (node (ref "M1") (pin "S16") (pinfunction "GND_S16") (pintype "passive"))
      (node (ref "M1") (pin "S25") (pinfunction "GND_S25") (pintype "passive"))
      (node (ref "M1") (pin "S3") (pinfunction "GND_S3") (pintype "passive"))
      (node (ref "M1") (pin "S34") (pinfunction "GND_S34") (pintype "passive"))
      (node (ref "M1") (pin "S47") (pinfunction "GND_S47") (pintype "passive"))
      (node (ref "M1") (pin "S61") (pinfunction "GND_S61") (pintype "passive"))
      (node (ref "M1") (pin "S64") (pinfunction "GND_S64") (pintype "passive"))
      (node (ref "M1") (pin "S67") (pinfunction "GND_S67") (pintype "passive"))
      (node (ref "M1") (pin "S70") (pinfunction "GND_S70") (pintype "passive"))
      (node (ref "M1") (pin "S73") (pinfunction "GND_S73") (pintype "passive"))
      (node (ref "M1") (pin "S80") (pinfunction "GND_S80") (pintype "passive"))
      (node (ref "M1") (pin "S83") (pinfunction "GND_S83") (pintype "passive"))
      (node (ref "M1") (pin "S86") (pinfunction "GND_S86") (pintype "passive"))
      (node (ref "M1") (pin "S89") (pinfunction "GND_S89") (pintype "passive"))
      (node (ref "M1") (pin "S92") (pinfunction "GND_S92") (pintype "passive"))
      (node (ref "MP1") (pin "1") (pinfunction "1_1") (pintype "passive"))
      (node (ref "MP2") (pin "1") (pinfunction "1_1") (pintype "passive"))
      (node (ref "MP3") (pin "1") (pinfunction "1_1") (pintype "passive"))
      (node (ref "MP4") (pin "1") (pinfunction "1_1") (pintype "passive"))
      (node (ref "R1") (pin "2") (pinfunction "2_2") (pintype "passive"))
      (node (ref "W1") (pin "3") (pinfunction "3_3") (pintype "bidirectional"))
      (node (ref "W2") (pin "4") (pinfunction "4_4") (pintype "bidirectional"))
    )
    (net (code "169") (name "Net-(M1B-RSVD-PadP72)") (class "Default")
      (node (ref "M1") (pin "P72") (pinfunction "RSVD_P72") (pintype "passive"))
      (node (ref "TP1") (pin "1") (pintype "passive"))
    )
    (net (code "170") (name "Net-(M1B-RSVD-PadP73)") (class "Default")
      (node (ref "M1") (pin "P73") (pinfunction "RSVD_P73") (pintype "passive"))
      (node (ref "TP2") (pin "1") (pintype "passive"))
    )
    (net (code "171") (name "P5V0_SMARC") (class "Default")
      (node (ref "C1") (pin "1") (pinfunction "1_1") (pintype "passive"))
      (node (ref "C10") (pin "2") (pinfunction "2_2") (pintype "passive"))
      (node (ref "C2") (pin "1") (pinfunction "1_1") (pintype "passive"))
      (node (ref "C3") (pin "1") (pinfunction "1_1") (pintype "passive"))
      (node (ref "C4") (pin "1") (pinfunction "1_1") (pintype "passive"))
      (node (ref "C5") (pin "2") (pinfunction "2_2") (pintype "passive"))
      (node (ref "C6") (pin "2") (pinfunction "2_2") (pintype "passive"))
      (node (ref "C7") (pin "2") (pinfunction "2_2") (pintype "passive"))
      (node (ref "C8") (pin "2") (pinfunction "2_2") (pintype "passive"))
      (node (ref "C9") (pin "2") (pinfunction "2_2") (pintype "passive"))
      (node (ref "M1") (pin "P147") (pinfunction "VDD_IN_P147") (pintype "passive"))
      (node (ref "M1") (pin "P148") (pinfunction "VDD_IN_P148") (pintype "passive"))
      (node (ref "M1") (pin "P149") (pinfunction "VDD_IN_P149") (pintype "passive"))
      (node (ref "M1") (pin "P150") (pinfunction "VDD_IN_P150") (pintype "passive"))
      (node (ref "M1") (pin "P151") (pinfunction "VDD_IN_P151") (pintype "passive"))
      (node (ref "M1") (pin "P152") (pinfunction "VDD_IN_P152") (pintype "passive"))
      (node (ref "M1") (pin "P153") (pinfunction "VDD_IN_P153") (pintype "passive"))
      (node (ref "M1") (pin "P154") (pinfunction "VDD_IN_P154") (pintype "passive"))
      (node (ref "M1") (pin "P155") (pinfunction "VDD_IN_P155") (pintype "passive"))
      (node (ref "M1") (pin "P156") (pinfunction "VDD_IN_P156") (pintype "passive"))
    )
    (net (code "172") (name "VCC_RTC") (class "Default")
      (node (ref "M1") (pin "S147") (pinfunction "VDD_RTC_S147") (pintype "passive"))
    )
    (net (code "173") (name "unconnected-(M1A-AUDIO_MCK-PadS38)") (class "Default")
      (node (ref "M1") (pin "S38") (pinfunction "AUDIO_MCK_S38") (pintype "passive"))
    )
    (net (code "174") (name "unconnected-(M1A-CAM_MCK-PadS6)") (class "Default")
      (node (ref "M1") (pin "S6") (pinfunction "CAM_MCK_S6") (pintype "passive"))
    )
    (net (code "175") (name "unconnected-(M1A-CSI0_CK+-PadS8)") (class "Default")
      (node (ref "M1") (pin "S8") (pinfunction "CSI0_CK+_S8") (pintype "passive"))
    )
    (net (code "176") (name "unconnected-(M1A-CSI0_CK--PadS9)") (class "Default")
      (node (ref "M1") (pin "S9") (pinfunction "CSI0_CK-_S9") (pintype "passive"))
    )
    (net (code "177") (name "unconnected-(M1A-CSI0_RX0+-PadS11)") (class "Default")
      (node (ref "M1") (pin "S11") (pinfunction "CSI0_RX0+_S11") (pintype "passive"))
    )
    (net (code "178") (name "unconnected-(M1A-CSI0_RX0--PadS12)") (class "Default")
      (node (ref "M1") (pin "S12") (pinfunction "CSI0_RX0-_S12") (pintype "passive"))
    )
    (net (code "179") (name "unconnected-(M1A-CSI0_RX1+-PadS14)") (class "Default")
      (node (ref "M1") (pin "S14") (pinfunction "CSI0_RX1+_S14") (pintype "passive"))
    )
    (net (code "180") (name "unconnected-(M1A-CSI0_RX1--PadS15)") (class "Default")
      (node (ref "M1") (pin "S15") (pinfunction "CSI0_RX1-_S15") (pintype "passive"))
    )
    (net (code "181") (name "unconnected-(M1A-CSI1_TX+{slash}I2C_CAM1_CK-PadS1)") (class "Default")
      (node (ref "M1") (pin "S1") (pinfunction "CSI1_TX+/I2C_CAM1_CK_S1") (pintype "passive"))
    )
    (net (code "182") (name "unconnected-(M1A-CSI1_TX-{slash}I2C_CAM1_DAT-PadS2)") (class "Default")
      (node (ref "M1") (pin "S2") (pinfunction "CSI1_TX-/I2C_CAM1_DAT_S2") (pintype "passive"))
    )
    (net (code "183") (name "unconnected-(M1A-ESPI_ALERT0#-PadS43)") (class "Default")
      (node (ref "M1") (pin "S43") (pinfunction "ESPI_ALERT0#_S43") (pintype "passive"))
    )
    (net (code "184") (name "unconnected-(M1A-ESPI_ALERT1#-PadS44)") (class "Default")
      (node (ref "M1") (pin "S44") (pinfunction "ESPI_ALERT1#_S44") (pintype "passive"))
    )
    (net (code "185") (name "unconnected-(M1A-ESPI_IO_2{slash}QSPI_IO_2-PadS56)") (class "Default")
      (node (ref "M1") (pin "S56") (pinfunction "ESPI_IO_2/QSPI_IO_2_S56") (pintype "passive"))
    )
    (net (code "186") (name "unconnected-(M1A-ESPI_IO_3{slash}QSPI_IO_3-PadS57)") (class "Default")
      (node (ref "M1") (pin "S57") (pinfunction "ESPI_IO_3/QSPI_IO_3_S57") (pintype "passive"))
    )
    (net (code "187") (name "unconnected-(M1A-ESPI_RESET#-PadS58)") (class "Default")
      (node (ref "M1") (pin "S58") (pinfunction "ESPI_RESET#_S58") (pintype "passive"))
    )
    (net (code "188") (name "unconnected-(M1A-I2C_CAM0_CK{slash}CSI0_TX+-PadS5)") (class "Default")
      (node (ref "M1") (pin "S5") (pinfunction "I2C_CAM0_CK/CSI0_TX+_S5") (pintype "passive"))
    )
    (net (code "189") (name "unconnected-(M1A-I2C_CAM0_DAT{slash}CSI0_TX--PadS7)") (class "Default")
      (node (ref "M1") (pin "S7") (pinfunction "I2C_CAM0_DAT/CSI0_TX-_S7") (pintype "passive"))
    )
    (net (code "190") (name "unconnected-(M1A-I2S0_CK-PadS42)") (class "Default")
      (node (ref "M1") (pin "S42") (pinfunction "I2S0_CK_S42") (pintype "passive"))
    )
    (net (code "191") (name "unconnected-(M1A-I2S0_LRCK-PadS39)") (class "Default")
      (node (ref "M1") (pin "S39") (pinfunction "I2S0_LRCK_S39") (pintype "passive"))
    )
    (net (code "192") (name "unconnected-(M1A-I2S0_SDIN-PadS41)") (class "Default")
      (node (ref "M1") (pin "S41") (pinfunction "I2S0_SDIN_S41") (pintype "passive"))
    )
    (net (code "193") (name "unconnected-(M1A-I2S0_SDOUT-PadS40)") (class "Default")
      (node (ref "M1") (pin "S40") (pinfunction "I2S0_SDOUT_S40") (pintype "passive"))
    )
    (net (code "194") (name "unconnected-(M1A-I2S2_CK{slash}HDA_CK-PadS53)") (class "Default")
      (node (ref "M1") (pin "S53") (pinfunction "I2S2_CK/HDA_CK_S53") (pintype "passive"))
    )
    (net (code "195") (name "unconnected-(M1A-I2S2_LRCK{slash}HDA_SYNC-PadS50)") (class "Default")
      (node (ref "M1") (pin "S50") (pinfunction "I2S2_LRCK/HDA_SYNC_S50") (pintype "passive"))
    )
    (net (code "196") (name "unconnected-(M1A-I2S2_SDIN{slash}HDA_SDI-PadS52)") (class "Default")
      (node (ref "M1") (pin "S52") (pinfunction "I2S2_SDIN/HDA_SDI_S52") (pintype "passive"))
    )
    (net (code "197") (name "unconnected-(M1A-I2S2_SDOUT{slash}HDA_SDO-PadS51)") (class "Default")
      (node (ref "M1") (pin "S51") (pinfunction "I2S2_SDOUT/HDA_SDO_S51") (pintype "passive"))
    )
    (net (code "198") (name "unconnected-(M1A-MDIO_CLK-PadS45)") (class "Default")
      (node (ref "M1") (pin "S45") (pinfunction "MDIO_CLK_S45") (pintype "passive"))
    )
    (net (code "199") (name "unconnected-(M1A-MDIO_DAT-PadS46)") (class "Default")
      (node (ref "M1") (pin "S46") (pinfunction "MDIO_DAT_S46") (pintype "passive"))
    )
    (net (code "200") (name "unconnected-(M1A-RSVD-PadS4)") (class "Default")
      (node (ref "M1") (pin "S4") (pinfunction "RSVD_S4") (pintype "passive"))
    )
    (net (code "201") (name "unconnected-(M1A-USB3_VBUS_DET-PadS37)") (class "Default")
      (node (ref "M1") (pin "S37") (pinfunction "USB3_VBUS_DET_S37") (pintype "passive"))
    )
    (net (code "202") (name "unconnected-(M1B-CSI1_CK+-PadP3)") (class "Default")
      (node (ref "M1") (pin "P3") (pinfunction "CSI1_CK+_P3") (pintype "passive"))
    )
    (net (code "203") (name "unconnected-(M1B-CSI1_CK--PadP4)") (class "Default")
      (node (ref "M1") (pin "P4") (pinfunction "CSI1_CK-_P4") (pintype "passive"))
    )
    (net (code "204") (name "unconnected-(M1B-CSI1_RX0+-PadP7)") (class "Default")
      (node (ref "M1") (pin "P7") (pinfunction "CSI1_RX0+_P7") (pintype "passive"))
    )
    (net (code "205") (name "unconnected-(M1B-CSI1_RX0--PadP8)") (class "Default")
      (node (ref "M1") (pin "P8") (pinfunction "CSI1_RX0-_P8") (pintype "passive"))
    )
    (net (code "206") (name "unconnected-(M1B-CSI1_RX1+-PadP10)") (class "Default")
      (node (ref "M1") (pin "P10") (pinfunction "CSI1_RX1+_P10") (pintype "passive"))
    )
    (net (code "207") (name "unconnected-(M1B-CSI1_RX1--PadP11)") (class "Default")
      (node (ref "M1") (pin "P11") (pinfunction "CSI1_RX1-_P11") (pintype "passive"))
    )
    (net (code "208") (name "unconnected-(M1B-CSI1_RX2+-PadP13)") (class "Default")
      (node (ref "M1") (pin "P13") (pinfunction "CSI1_RX2+_P13") (pintype "passive"))
    )
    (net (code "209") (name "unconnected-(M1B-CSI1_RX2--PadP14)") (class "Default")
      (node (ref "M1") (pin "P14") (pinfunction "CSI1_RX2-_P14") (pintype "passive"))
    )
    (net (code "210") (name "unconnected-(M1B-CSI1_RX3+-PadP16)") (class "Default")
      (node (ref "M1") (pin "P16") (pinfunction "CSI1_RX3+_P16") (pintype "passive"))
    )
    (net (code "211") (name "unconnected-(M1B-CSI1_RX3--PadP17)") (class "Default")
      (node (ref "M1") (pin "P17") (pinfunction "CSI1_RX3-_P17") (pintype "passive"))
    )
    (net (code "212") (name "unconnected-(M1B-GBE0_SDP-PadP6)") (class "Default")
      (node (ref "M1") (pin "P6") (pinfunction "GBE0_SDP_P6") (pintype "passive"))
    )
    (net (code "213") (name "unconnected-(M1B-GBE1_SDP-PadP5)") (class "Default")
      (node (ref "M1") (pin "P5") (pinfunction "GBE1_SDP_P5") (pintype "passive"))
    )
    (net (code "214") (name "unconnected-(M1B-GND-PadP12)") (class "Default")
      (node (ref "M1") (pin "P12") (pinfunction "GND_P12") (pintype "passive"))
    )
    (net (code "215") (name "unconnected-(M1B-SDIO_CD#-PadP35)") (class "Default")
      (node (ref "M1") (pin "P35") (pinfunction "SDIO_CD#_P35") (pintype "passive"))
    )
    (net (code "216") (name "unconnected-(M1B-SDIO_CK-PadP36)") (class "Default")
      (node (ref "M1") (pin "P36") (pinfunction "SDIO_CK_P36") (pintype "passive"))
    )
    (net (code "217") (name "unconnected-(M1B-SDIO_CMD-PadP34)") (class "Default")
      (node (ref "M1") (pin "P34") (pinfunction "SDIO_CMD_P34") (pintype "passive"))
    )
    (net (code "218") (name "unconnected-(M1B-SDIO_D0-PadP39)") (class "Default")
      (node (ref "M1") (pin "P39") (pinfunction "SDIO_D0_P39") (pintype "passive"))
    )
    (net (code "219") (name "unconnected-(M1B-SDIO_D1-PadP40)") (class "Default")
      (node (ref "M1") (pin "P40") (pinfunction "SDIO_D1_P40") (pintype "passive"))
    )
    (net (code "220") (name "unconnected-(M1B-SDIO_D2-PadP41)") (class "Default")
      (node (ref "M1") (pin "P41") (pinfunction "SDIO_D2_P41") (pintype "passive"))
    )
    (net (code "221") (name "unconnected-(M1B-SDIO_D3-PadP42)") (class "Default")
      (node (ref "M1") (pin "P42") (pinfunction "SDIO_D3_P42") (pintype "passive"))
    )
    (net (code "222") (name "unconnected-(M1B-SDIO_PWR_EN-PadP37)") (class "Default")
      (node (ref "M1") (pin "P37") (pinfunction "SDIO_PWR_EN_P37") (pintype "passive"))
    )
    (net (code "223") (name "unconnected-(M1B-SDIO_WP-PadP33)") (class "Default")
      (node (ref "M1") (pin "P33") (pinfunction "SDIO_WP_P33") (pintype "passive"))
    )
    (net (code "224") (name "unconnected-(M1B-SPI0_CK-PadP44)") (class "Default")
      (node (ref "M1") (pin "P44") (pinfunction "SPI0_CK_P44") (pintype "passive"))
    )
    (net (code "225") (name "unconnected-(M1B-SPI0_CS0#-PadP43)") (class "Default")
      (node (ref "M1") (pin "P43") (pinfunction "SPI0_CS0#_P43") (pintype "passive"))
    )
    (net (code "226") (name "unconnected-(M1B-SPI0_CS1#-PadP31)") (class "Default")
      (node (ref "M1") (pin "P31") (pinfunction "SPI0_CS1#_P31") (pintype "passive"))
    )
    (net (code "227") (name "unconnected-(M1B-SPI0_DIN-PadP45)") (class "Default")
      (node (ref "M1") (pin "P45") (pinfunction "SPI0_DIN_P45") (pintype "passive"))
    )
    (net (code "228") (name "unconnected-(M1B-SPI0_DO-PadP46)") (class "Default")
      (node (ref "M1") (pin "P46") (pinfunction "SPI0_DO_P46") (pintype "passive"))
    )
    (net (code "229") (name "unconnected-(M1B-SPI1_CK{slash}ESPI_CK{slash}QSPI_CK-PadP56)") (class "Default")
      (node (ref "M1") (pin "P56") (pinfunction "SPI1_CK/ESPI_CK/QSPI_CK_P56") (pintype "passive"))
    )
    (net (code "230") (name "unconnected-(M1B-SPI1_CS0#{slash}ESPI_CS0#{slash}QSPI_CS0#-PadP54)") (class "Default")
      (node (ref "M1") (pin "P54") (pinfunction "SPI1_CS0#/ESPI_CS0#/QSPI_CS0#_P54") (pintype "passive"))
    )
    (net (code "231") (name "unconnected-(M1B-SPI1_CS1#{slash}ESPI_CS1#{slash}QSPI_CS1#-PadP55)") (class "Default")
      (node (ref "M1") (pin "P55") (pinfunction "SPI1_CS1#/ESPI_CS1#/QSPI_CS1#_P55") (pintype "passive"))
    )
    (net (code "232") (name "unconnected-(M1B-SPI1_DIN{slash}ESPI_IO_1{slash}QSPI_IO_1-PadP57)") (class "Default")
      (node (ref "M1") (pin "P57") (pinfunction "SPI1_DIN/ESPI_IO_1/QSPI_IO_1_P57") (pintype "passive"))
    )
    (net (code "233") (name "unconnected-(M1B-SPI1_DO{slash}ESPI_IO_0{slash}QSPI_IO_0-PadP58)") (class "Default")
      (node (ref "M1") (pin "P58") (pinfunction "SPI1_DO/ESPI_IO_0/QSPI_IO_0_P58") (pintype "passive"))
    )
    (net (code "234") (name "unconnected-(M1B-USB0_OTG_ID-PadP64)") (class "Default")
      (node (ref "M1") (pin "P64") (pinfunction "USB0_OTG_ID_P64") (pintype "passive"))
    )
    (net (code "235") (name "unconnected-(M1B-USB0_VBUS_DET-PadP63)") (class "Default")
      (node (ref "M1") (pin "P63") (pinfunction "USB0_VBUS_DET_P63") (pintype "passive"))
    )
    (net (code "236") (name "unconnected-(M1C-GPIO12-PadS142)") (class "Default")
      (node (ref "M1") (pin "S142") (pinfunction "GPIO12_S142") (pintype "passive"))
    )
    (net (code "237") (name "unconnected-(M1C-GPIO13-PadS123)") (class "Default")
      (node (ref "M1") (pin "S123") (pinfunction "GPIO13_S123") (pintype "passive"))
    )
    (net (code "238") (name "unconnected-(M1C-I2C_LCD_CK-PadS139)") (class "Default")
      (node (ref "M1") (pin "S139") (pinfunction "I2C_LCD_CK_S139") (pintype "passive"))
    )
    (net (code "239") (name "unconnected-(M1C-I2C_LCD_DAT-PadS140)") (class "Default")
      (node (ref "M1") (pin "S140") (pinfunction "I2C_LCD_DAT_S140") (pintype "passive"))
    )
    (net (code "240") (name "unconnected-(M1C-LCD0_BKLT_EN-PadS127)") (class "Default")
      (node (ref "M1") (pin "S127") (pinfunction "LCD0_BKLT_EN_S127") (pintype "passive"))
    )
    (net (code "241") (name "unconnected-(M1C-LCD0_BKLT_PWM-PadS141)") (class "Default")
      (node (ref "M1") (pin "S141") (pinfunction "LCD0_BKLT_PWM_S141") (pintype "passive"))
    )
    (net (code "242") (name "unconnected-(M1C-LCD0_VDD_EN-PadS133)") (class "Default")
      (node (ref "M1") (pin "S133") (pinfunction "LCD0_VDD_EN_S133") (pintype "passive"))
    )
    (net (code "243") (name "unconnected-(M1C-LCD1_BKLT_EN-PadS107)") (class "Default")
      (node (ref "M1") (pin "S107") (pinfunction "LCD1_BKLT_EN_S107") (pintype "passive"))
    )
    (net (code "244") (name "unconnected-(M1C-LCD1_BKLT_PWM-PadS122)") (class "Default")
      (node (ref "M1") (pin "S122") (pinfunction "LCD1_BKLT_PWM_S122") (pintype "passive"))
    )
    (net (code "245") (name "unconnected-(M1C-LCD1_VDD_EN-PadS116)") (class "Default")
      (node (ref "M1") (pin "S116") (pinfunction "LCD1_VDD_EN_S116") (pintype "passive"))
    )
    (net (code "246") (name "unconnected-(M1C-LVDS0_0+{slash}eDP0_TX0+{slash}DSI0_D0+-PadS125)") (class "Default")
      (node (ref "M1") (pin "S125") (pinfunction "LVDS0_0+/eDP0_TX0+/DSI0_D0+_S125") (pintype "passive"))
    )
    (net (code "247") (name "unconnected-(M1C-LVDS0_0-{slash}eDP0_TX0-{slash}DSI0_D0--PadS126)") (class "Default")
      (node (ref "M1") (pin "S126") (pinfunction "LVDS0_0-/eDP0_TX0-/DSI0_D0-_S126") (pintype "passive"))
    )
    (net (code "248") (name "unconnected-(M1C-LVDS0_1+{slash}eDP0_TX1+{slash}DSI0_D1+-PadS128)") (class "Default")
      (node (ref "M1") (pin "S128") (pinfunction "LVDS0_1+/eDP0_TX1+/DSI0_D1+_S128") (pintype "passive"))
    )
    (net (code "249") (name "unconnected-(M1C-LVDS0_1-{slash}eDP0_TX1-{slash}DSI0_D1--PadS129)") (class "Default")
      (node (ref "M1") (pin "S129") (pinfunction "LVDS0_1-/eDP0_TX1-/DSI0_D1-_S129") (pintype "passive"))
    )
    (net (code "250") (name "unconnected-(M1C-LVDS0_2+{slash}eDP0_TX2+{slash}DSI0_D2+-PadS131)") (class "Default")
      (node (ref "M1") (pin "S131") (pinfunction "LVDS0_2+/eDP0_TX2+/DSI0_D2+_S131") (pintype "passive"))
    )
    (net (code "251") (name "unconnected-(M1C-LVDS0_2-{slash}eDP0_TX2-{slash}DSI0_D2--PadS132)") (class "Default")
      (node (ref "M1") (pin "S132") (pinfunction "LVDS0_2-/eDP0_TX2-/DSI0_D2-_S132") (pintype "passive"))
    )
    (net (code "252") (name "unconnected-(M1C-LVDS0_3+{slash}eDP0_TX3+{slash}DSI0_D3+-PadS137)") (class "Default")
      (node (ref "M1") (pin "S137") (pinfunction "LVDS0_3+/eDP0_TX3+/DSI0_D3+_S137") (pintype "passive"))
    )
    (net (code "253") (name "unconnected-(M1C-LVDS0_3-{slash}eDP0_TX3-{slash}DSI0_D3--PadS138)") (class "Default")
      (node (ref "M1") (pin "S138") (pinfunction "LVDS0_3-/eDP0_TX3-/DSI0_D3-_S138") (pintype "passive"))
    )
    (net (code "254") (name "unconnected-(M1C-LVDS0_CK+{slash}eDP0_AUX+{slash}DSI0_CLK+-PadS134)") (class "Default")
      (node (ref "M1") (pin "S134") (pinfunction "LVDS0_CK+/eDP0_AUX+/DSI0_CLK+_S134") (pintype "passive"))
    )
    (net (code "255") (name "unconnected-(M1C-LVDS0_CK-{slash}eDP0_AUX-{slash}DSI0_CLK--PadS135)") (class "Default")
      (node (ref "M1") (pin "S135") (pinfunction "LVDS0_CK-/eDP0_AUX-/DSI0_CLK-_S135") (pintype "passive"))
    )
    (net (code "256") (name "unconnected-(M1C-LVDS1_0+{slash}eDP1_TX0+{slash}DSI1_D0+-PadS111)") (class "Default")
      (node (ref "M1") (pin "S111") (pinfunction "LVDS1_0+/eDP1_TX0+/DSI1_D0+_S111") (pintype "passive"))
    )
    (net (code "257") (name "unconnected-(M1C-LVDS1_0-{slash}eDP1_TX0-{slash}DSI1_D0--PadS112)") (class "Default")
      (node (ref "M1") (pin "S112") (pinfunction "LVDS1_0-/eDP1_TX0-/DSI1_D0-_S112") (pintype "passive"))
    )
    (net (code "258") (name "unconnected-(M1C-LVDS1_1+{slash}eDP1_TX1+{slash}DSI1_D1+-PadS114)") (class "Default")
      (node (ref "M1") (pin "S114") (pinfunction "LVDS1_1+/eDP1_TX1+/DSI1_D1+_S114") (pintype "passive"))
    )
    (net (code "259") (name "unconnected-(M1C-LVDS1_1-{slash}eDP1_TX1-{slash}DSI1_D1--PadS115)") (class "Default")
      (node (ref "M1") (pin "S115") (pinfunction "LVDS1_1-/eDP1_TX1-/DSI1_D1-_S115") (pintype "passive"))
    )
    (net (code "260") (name "unconnected-(M1C-LVDS1_2+{slash}eDP1_TX2+{slash}DSI1_D2+-PadS117)") (class "Default")
      (node (ref "M1") (pin "S117") (pinfunction "LVDS1_2+/eDP1_TX2+/DSI1_D2+_S117") (pintype "passive"))
    )
    (net (code "261") (name "unconnected-(M1C-LVDS1_2-{slash}eDP1_TX2-{slash}DSI1_D2--PadS118)") (class "Default")
      (node (ref "M1") (pin "S118") (pinfunction "LVDS1_2-/eDP1_TX2-/DSI1_D2-_S118") (pintype "passive"))
    )
    (net (code "262") (name "unconnected-(M1C-LVDS1_3+{slash}eDP1_TX3+{slash}DSI1_D3+-PadS120)") (class "Default")
      (node (ref "M1") (pin "S120") (pinfunction "LVDS1_3+/eDP1_TX3+/DSI1_D3+_S120") (pintype "passive"))
    )
    (net (code "263") (name "unconnected-(M1C-LVDS1_3-{slash}eDP1_TX3-{slash}DSI1_D3--PadS121)") (class "Default")
      (node (ref "M1") (pin "S121") (pinfunction "LVDS1_3-/eDP1_TX3-/DSI1_D3-_S121") (pintype "passive"))
    )
    (net (code "264") (name "unconnected-(M1C-LVDS1_CK+{slash}eDP1_AUX+{slash}DSI1_CLK+-PadS108)") (class "Default")
      (node (ref "M1") (pin "S108") (pinfunction "LVDS1_CK+/eDP1_AUX+/DSI1_CLK+_S108") (pintype "passive"))
    )
    (net (code "265") (name "unconnected-(M1C-LVDS1_CK-{slash}eDP1_AUX-{slash}DSI1_CLK--PadS109)") (class "Default")
      (node (ref "M1") (pin "S109") (pinfunction "LVDS1_CK-/eDP1_AUX-/DSI1_CLK-_S109") (pintype "passive"))
    )
    (net (code "266") (name "unconnected-(M1C-TEST#-PadS157)") (class "Default")
      (node (ref "M1") (pin "S157") (pinfunction "TEST#_S157") (pintype "passive"))
    )
    (net (code "267") (name "unconnected-(M1C-USB3_OTG_ID-PadS104)") (class "Default")
      (node (ref "M1") (pin "S104") (pinfunction "USB3_OTG_ID_S104") (pintype "passive"))
    )
    (net (code "268") (name "unconnected-(M1C-eDP0_HPD{slash}DSI0_TE-PadS144)") (class "Default")
      (node (ref "M1") (pin "S144") (pinfunction "eDP0_HPD/DSI0_TE_S144") (pintype "passive"))
    )
    (net (code "269") (name "unconnected-(M1C-eDP1_HPD{slash}DSI1_TE-PadS113)") (class "Default")
      (node (ref "M1") (pin "S113") (pinfunction "eDP1_HPD/DSI1_TE_S113") (pintype "passive"))
    )
    (net (code "270") (name "unconnected-(M1D-CAN0_RX-PadP144)") (class "Default")
      (node (ref "M1") (pin "P144") (pinfunction "CAN0_RX_P144") (pintype "passive"))
    )
    (net (code "271") (name "unconnected-(M1D-CAN0_TX-PadP143)") (class "Default")
      (node (ref "M1") (pin "P143") (pinfunction "CAN0_TX_P143") (pintype "passive"))
    )
    (net (code "272") (name "unconnected-(M1D-CAN1_RX-PadP146)") (class "Default")
      (node (ref "M1") (pin "P146") (pinfunction "CAN1_RX_P146") (pintype "passive"))
    )
    (net (code "273") (name "unconnected-(M1D-CAN1_TX-PadP145)") (class "Default")
      (node (ref "M1") (pin "P145") (pinfunction "CAN1_TX_P145") (pintype "passive"))
    )
    (net (code "274") (name "unconnected-(M1D-GPIO8-PadP116)") (class "Default")
      (node (ref "M1") (pin "P116") (pinfunction "GPIO8_P116") (pintype "passive"))
    )
    (net (code "275") (name "unconnected-(M1D-GPIO9-PadP117)") (class "Default")
      (node (ref "M1") (pin "P117") (pinfunction "GPIO9_P117") (pintype "passive"))
    )
    (net (code "276") (name "unconnected-(M1D-GPIO10-PadP118)") (class "Default")
      (node (ref "M1") (pin "P118") (pinfunction "GPIO10_P118") (pintype "passive"))
    )
    (net (code "277") (name "unconnected-(M1D-GPIO11-PadP119)") (class "Default")
      (node (ref "M1") (pin "P119") (pinfunction "GPIO11_P119") (pintype "passive"))
    )
    (net (code "278") (name "unconnected-(M1D-SER1_RX-PadP135)") (class "Default")
      (node (ref "M1") (pin "P135") (pinfunction "SER1_RX_P135") (pintype "passive"))
    )
    (net (code "279") (name "unconnected-(M1D-SER1_TX-PadP134)") (class "Default")
      (node (ref "M1") (pin "P134") (pinfunction "SER1_TX_P134") (pintype "passive"))
    )
    (net (code "280") (name "unconnected-(M1D-SER3_RX-PadP141)") (class "Default")
      (node (ref "M1") (pin "P141") (pinfunction "SER3_RX_P141") (pintype "passive"))
    )
    (net (code "281") (name "unconnected-(M1D-SER3_TX-PadP140)") (class "Default")
      (node (ref "M1") (pin "P140") (pinfunction "SER3_TX_P140") (pintype "passive"))
    )
  )
)
